# SCH_directMessage.net
KiCad netlist of a schematic drawn in EasyEDA
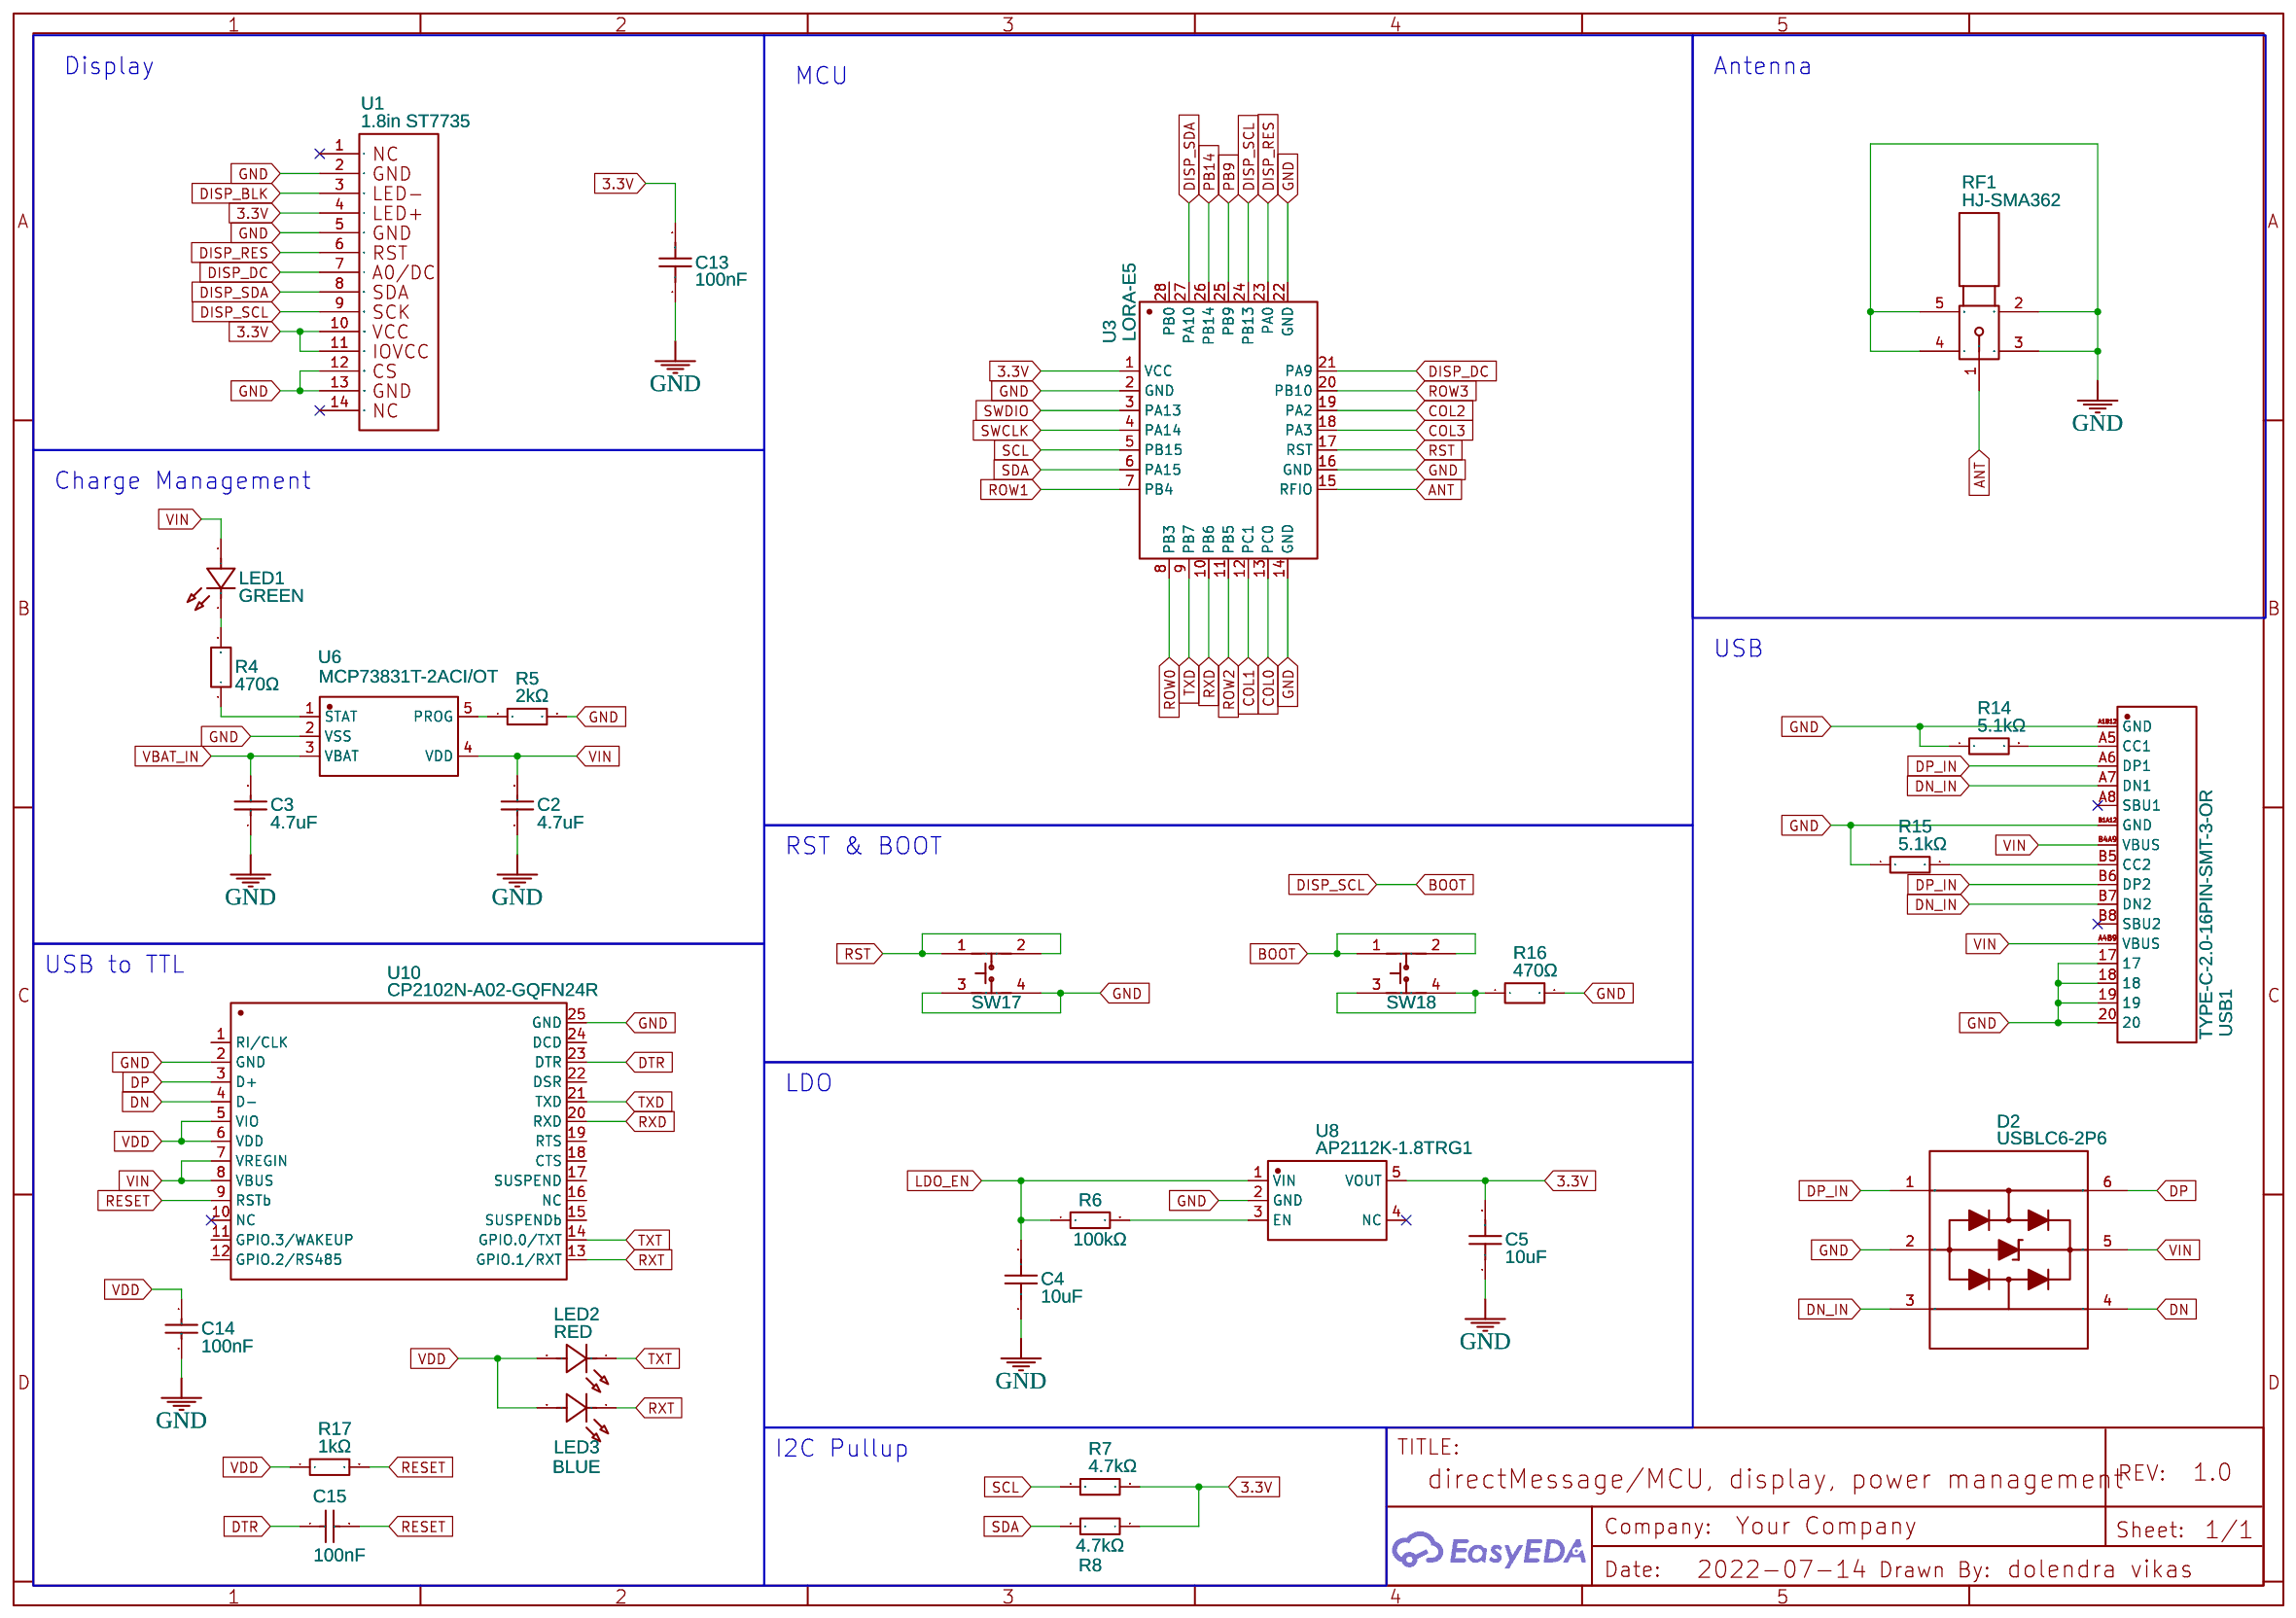
[diagram p0: Sheet_1]
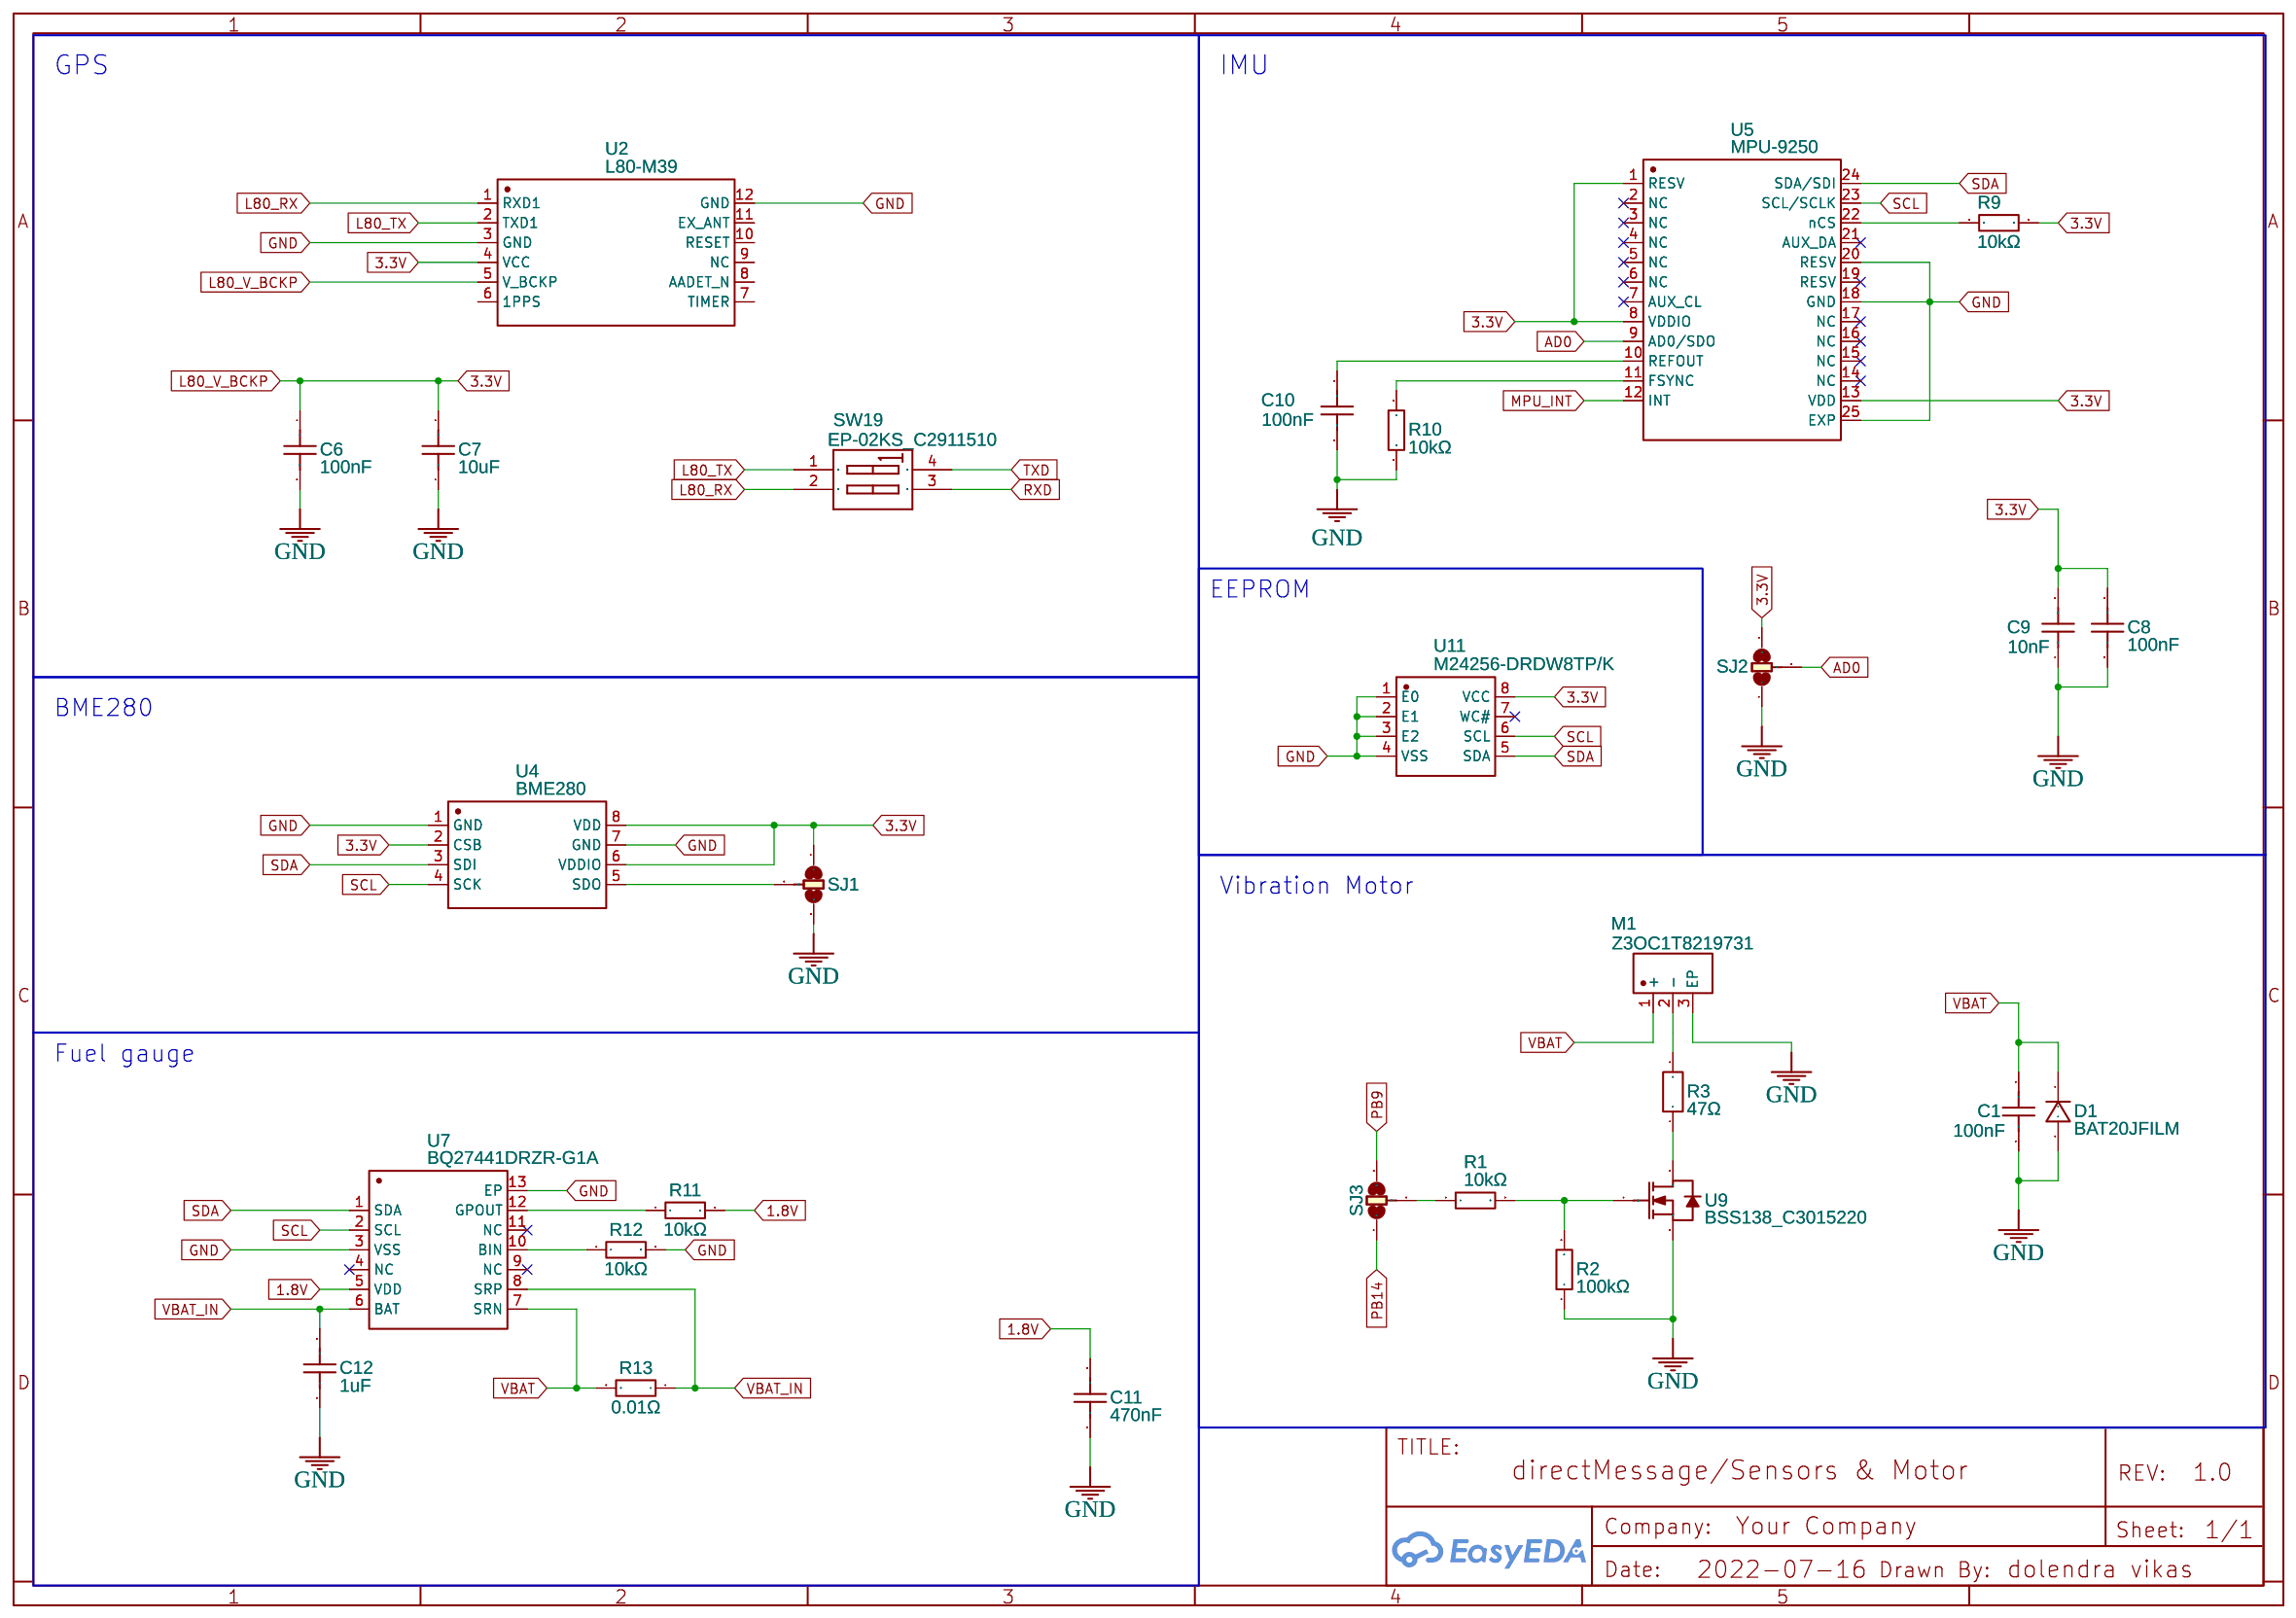
[diagram p1: Sheet_2]
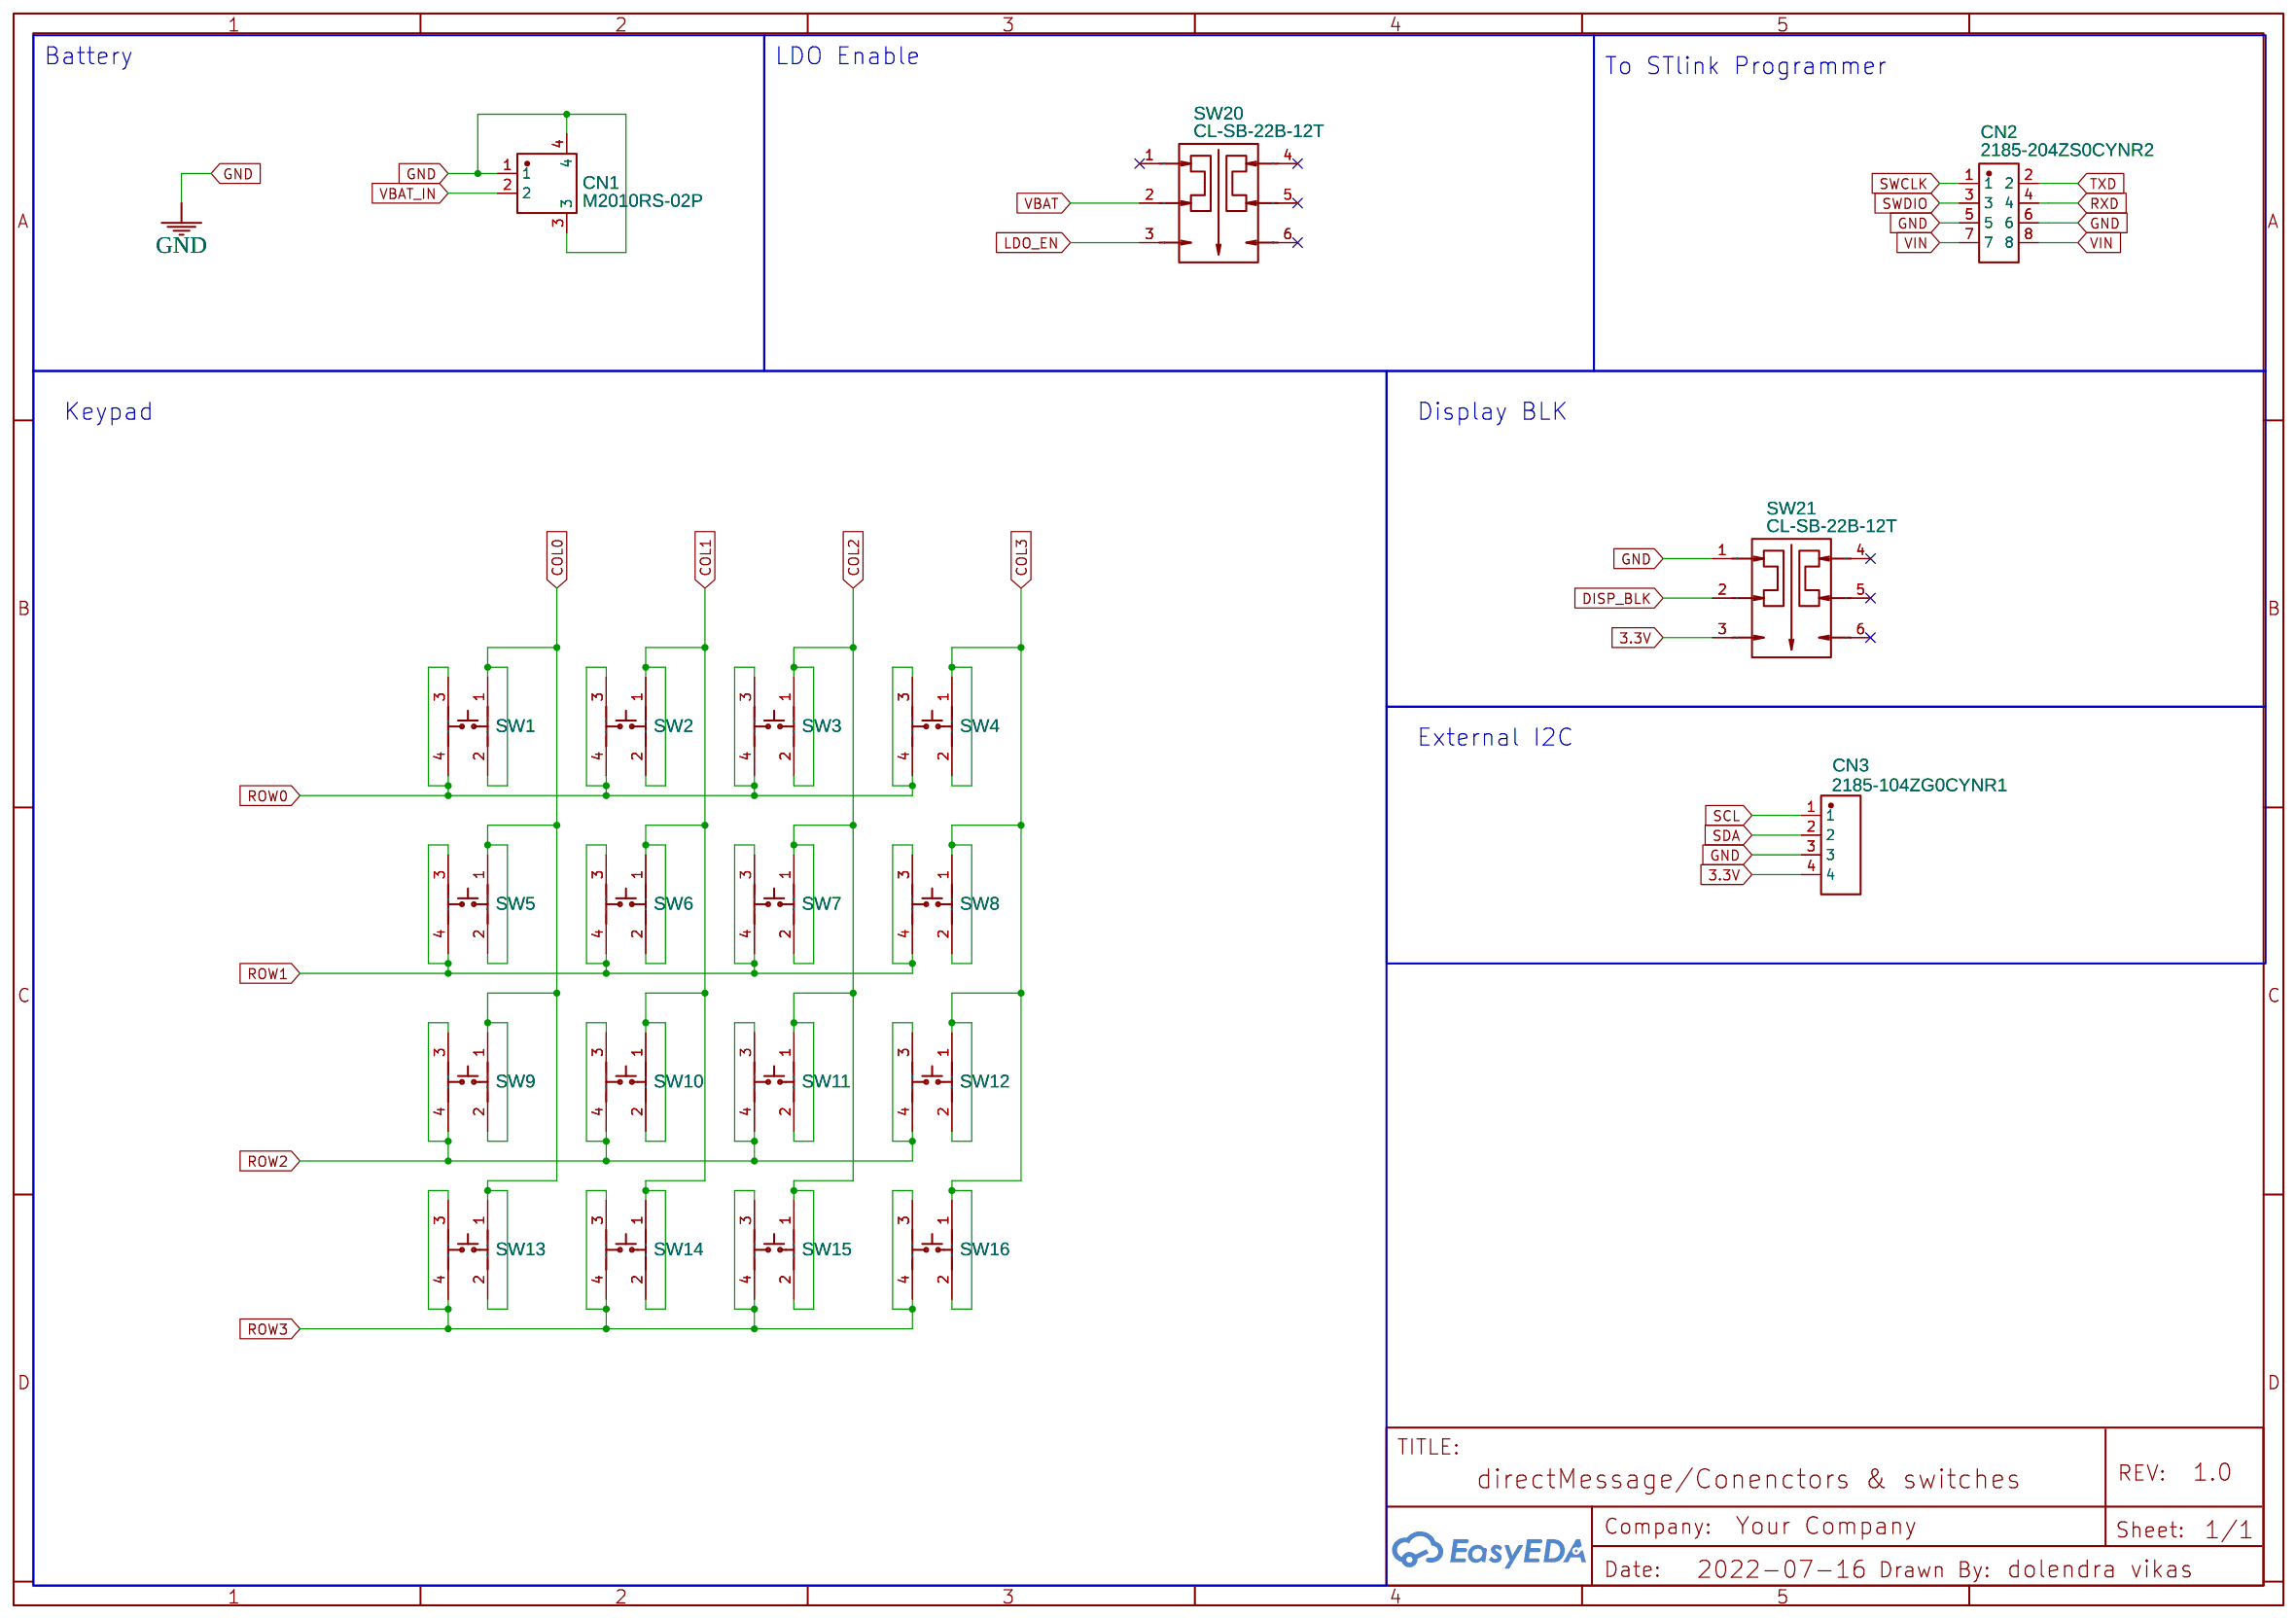
[diagram p2: Sheet_3]

(export (version "E")
  (design (tool "Eeschema 10.0.6"))
  (components
    (comp (ref "C2")
      (value "4.7uF")
      (fields
        (field (name "BOM_Manufacturer Part") "0603F475M100NT")
        (field (name "BOM_Supplier Part") "C108344")
      )
      (libsource (lib "") (part "0603 4.7UF CAPACITOR (SMD)"))
    )
    (comp (ref "C3")
      (value "4.7uF")
      (fields
        (field (name "BOM_Manufacturer Part") "0603F475M100NT")
        (field (name "BOM_Supplier Part") "C108344")
      )
      (libsource (lib "") (part "0603 4.7UF CAPACITOR (SMD)"))
    )
    (comp (ref "C4")
      (value "10uF")
      (fields
        (field (name "BOM_Manufacturer Part") "0603X106M6R3")
        (field (name "BOM_Supplier Part") "C123608")
      )
      (libsource (lib "") (part "0603X106M6R3"))
    )
    (comp (ref "C5")
      (value "10uF")
      (fields
        (field (name "BOM_Manufacturer Part") "0603X106M6R3")
        (field (name "BOM_Supplier Part") "C123608")
      )
      (libsource (lib "") (part "0603X106M6R3"))
    )
    (comp (ref "C13")
      (value "100nF")
      (fields
        (field (name "BOM_Manufacturer Part") "GCM188R71H104KA57D")
        (field (name "BOM_Supplier Part") "C85864")
      )
      (libsource (lib "") (part "GCM188R71H104KA57D"))
    )
    (comp (ref "C14")
      (value "100nF")
      (fields
        (field (name "BOM_Manufacturer Part") "FN18X104K500PBG")
        (field (name "BOM_Supplier Part") "C235731")
      )
      (libsource (lib "") (part "FN18X104K500PBG_1"))
    )
    (comp (ref "C15")
      (value "100nF")
      (fields
        (field (name "BOM_Manufacturer Part") "FN18X104K500PBG")
        (field (name "BOM_Supplier Part") "C235731")
      )
      (libsource (lib "") (part "FN18X104K500PBG"))
    )
    (comp (ref "D2")
      (value "USBLC6-2P6")
      (fields (field (name "BOM_Supplier Part") "C15999"))
      (libsource (lib "") (part "USBLC6-2P6"))
    )
    (comp (ref "LED1")
      (value "GREEN")
      (fields
        (field (name "BOM_Manufacturer Part") "XL-1608SYGC-06")
        (field (name "BOM_Supplier Part") "C965805")
      )
      (libsource (lib "") (part "XL-1608SYGC-06"))
    )
    (comp (ref "LED2")
      (value "RED")
      (fields
        (field (name "BOM_Manufacturer Part") "XL-1608SURC-06")
        (field (name "BOM_Supplier Part") "C965799")
      )
      (libsource (lib "") (part "XL-1608SURC-06"))
    )
    (comp (ref "LED3")
      (value "BLUE")
      (fields
        (field (name "BOM_Manufacturer Part") "XL-1608UBC-04")
        (field (name "BOM_Supplier Part") "C965807")
      )
      (libsource (lib "") (part "XL-1608UBC-04"))
    )
    (comp (ref "R4")
      (value "470Ω")
      (fields
        (field (name "BOM_Manufacturer Part") "ERJPA3J471V")
        (field (name "BOM_Supplier Part") "C441888")
      )
      (libsource (lib "") (part "ERJPA3J471V_1"))
    )
    (comp (ref "R5")
      (value "2kΩ")
      (fields
        (field (name "BOM_Manufacturer Part") "ERJ-3EKF2001V")
        (field (name "BOM_Supplier Part") "C192167")
      )
      (libsource (lib "") (part "ERJ-3EKF2001V"))
    )
    (comp (ref "R6")
      (value "100kΩ")
      (fields
        (field (name "BOM_Manufacturer Part") "ERJ3EKF1003V")
        (field (name "BOM_Supplier Part") "C189597")
      )
      (libsource (lib "") (part "ERJ3EKF1003V"))
    )
    (comp (ref "R7")
      (value "4.7kΩ")
      (fields
        (field (name "BOM_Manufacturer Part") "ERJ-3RBD4701V")
        (field (name "BOM_Supplier Part") "C191778")
      )
      (libsource (lib "") (part "ERJ-3RBD4701V_1"))
    )
    (comp (ref "R8")
      (value "4.7kΩ")
      (fields
        (field (name "BOM_Manufacturer Part") "ERJ-3RBD4701V")
        (field (name "BOM_Supplier Part") "C191778")
      )
      (libsource (lib "") (part "ERJ-3RBD4701V"))
    )
    (comp (ref "R14")
      (value "5.1kΩ")
      (fields
        (field (name "BOM_Manufacturer Part") "ERJ-3RBD5101V")
        (field (name "BOM_Supplier Part") "C191782")
      )
      (libsource (lib "") (part "ERJ-3RBD5101V"))
    )
    (comp (ref "R15")
      (value "5.1kΩ")
      (fields
        (field (name "BOM_Manufacturer Part") "ERJ-3RBD5101V")
        (field (name "BOM_Supplier Part") "C191782")
      )
      (libsource (lib "") (part "ERJ-3RBD5101V"))
    )
    (comp (ref "R16")
      (value "470Ω")
      (fields
        (field (name "BOM_Manufacturer Part") "ERJPA3J471V")
        (field (name "BOM_Supplier Part") "C441888")
      )
      (libsource (lib "") (part "ERJPA3J471V"))
    )
    (comp (ref "R17")
      (value "1kΩ")
      (fields
        (field (name "BOM_Manufacturer Part") "ERJ-3EKF1001V")
        (field (name "BOM_Supplier Part") "C118155")
      )
      (libsource (lib "") (part "ERJ-3EKF1001V"))
    )
    (comp (ref "RF1")
      (value "HJ-SMA362")
      (fields (field (name "BOM_Supplier Part") "C2905338"))
      (libsource (lib "") (part "HJ-SMA362"))
    )
    (comp (ref "SW17")
      (value "SKRPABE010")
      (fields (field (name "BOM_Supplier Part") "C115360"))
      (libsource (lib "") (part "SKRPABE010"))
    )
    (comp (ref "SW18")
      (value "SKRPABE010")
      (fields (field (name "BOM_Supplier Part") "C115360"))
      (libsource (lib "") (part "SKRPABE010"))
    )
    (comp (ref "U1") (value "1.8in ST7735") (libsource (lib "") (part "1.8in ST7735")))
    (comp (ref "U3")
      (value "LORA-E5")
      (fields
        (field (name "BOM_Manufacturer Part") "LoRa-E5")
        (field (name "BOM_Supplier Part") "C9900002286")
      )
      (libsource (lib "") (part "LORA-E5"))
    )
    (comp (ref "U6")
      (value "MCP73831T-2ACI/OT")
      (fields (field (name "BOM_Supplier Part") "C424093"))
      (libsource (lib "") (part "MCP73831T-2ACI/OT"))
    )
    (comp (ref "U8")
      (value "AP2112K-1.8TRG1")
      (fields (field (name "BOM_Supplier Part") "C176944"))
      (libsource (lib "") (part "AP2112K-1.8TRG1"))
    )
    (comp (ref "U10")
      (value "CP2102N-A02-GQFN24R")
      (fields (field (name "BOM_Supplier Part") "C969151"))
      (libsource (lib "") (part "CP2102N-A02-GQFN24R"))
    )
    (comp (ref "USB1")
      (value "TYPE-C-2.0-16PIN-SMT-3-OR")
      (fields (field (name "BOM_Supplier Part") "C2987387"))
      (libsource (lib "") (part "TYPE-C-2.0-16PIN-SMT-3-OR"))
    )
    (comp (ref "C1")
      (value "100nF")
      (fields
        (field (name "BOM_Manufacturer Part") "C0603C104J5RAC")
        (field (name "BOM_Supplier Part") "C490602")
      )
      (libsource (lib "") (part "C0603C104J5RAC"))
    )
    (comp (ref "C6")
      (value "100nF")
      (fields
        (field (name "BOM_Manufacturer Part") "C0603C104J5RAC")
        (field (name "BOM_Supplier Part") "C490602")
      )
      (libsource (lib "") (part "C0603C104J5RAC"))
    )
    (comp (ref "C7")
      (value "10uF")
      (fields
        (field (name "BOM_Manufacturer Part") "0603X106M6R3")
        (field (name "BOM_Supplier Part") "C123608")
      )
      (libsource (lib "") (part "0603X106M6R3"))
    )
    (comp (ref "C8")
      (value "100nF")
      (fields
        (field (name "BOM_Manufacturer Part") "C0603C104J5RAC")
        (field (name "BOM_Supplier Part") "C490602")
      )
      (libsource (lib "") (part "C0603C104J5RAC"))
    )
    (comp (ref "C9")
      (value "10nF")
      (fields
        (field (name "BOM_Manufacturer Part") "C0603C103J3GAC7867")
        (field (name "BOM_Supplier Part") "C140951")
      )
      (libsource (lib "") (part "C0603C103J3GAC7867"))
    )
    (comp (ref "C10")
      (value "100nF")
      (fields
        (field (name "BOM_Manufacturer Part") "C0603C104J5RAC")
        (field (name "BOM_Supplier Part") "C490602")
      )
      (libsource (lib "") (part "C0603C104J5RAC"))
    )
    (comp (ref "C11")
      (value "470nF")
      (fields
        (field (name "BOM_Manufacturer Part") "GCM188R71E474KA64D")
        (field (name "BOM_Supplier Part") "C161219")
      )
      (libsource (lib "") (part "GCM188R71E474KA64D"))
    )
    (comp (ref "C12")
      (value "1uF")
      (fields
        (field (name "BOM_Manufacturer Part") "GRM188R61E105KA12D")
        (field (name "BOM_Supplier Part") "C77046")
      )
      (libsource (lib "") (part "GRM188R61E105KA12D"))
    )
    (comp (ref "D1")
      (value "BAT20JFILM")
      (fields (field (name "BOM_Supplier Part") "C155590"))
      (libsource (lib "") (part "BAT20JFILM"))
    )
    (comp (ref "M1")
      (value "Z3OC1T8219731")
      (fields (field (name "BOM_Supplier Part") "C2894731"))
      (libsource (lib "") (part "Z3OC1T8219731"))
    )
    (comp (ref "R1")
      (value "10kΩ")
      (fields
        (field (name "BOM_Manufacturer Part") "ERJ3GEYJ103V")
        (field (name "BOM_Supplier Part") "C169849")
      )
      (libsource (lib "") (part "ERJ3GEYJ103V_1"))
    )
    (comp (ref "R2")
      (value "100kΩ")
      (fields
        (field (name "BOM_Manufacturer Part") "ERJ3EKF1003V")
        (field (name "BOM_Supplier Part") "C189597")
      )
      (libsource (lib "") (part "ERJ3EKF1003V"))
    )
    (comp (ref "R3")
      (value "47Ω")
      (fields
        (field (name "BOM_Manufacturer Part") "ERJUP3D47R0V")
        (field (name "BOM_Supplier Part") "C491217")
      )
      (libsource (lib "") (part "ERJUP3D47R0V"))
    )
    (comp (ref "R9")
      (value "10kΩ")
      (fields
        (field (name "BOM_Manufacturer Part") "ERJ3GEYJ103V")
        (field (name "BOM_Supplier Part") "C169849")
      )
      (libsource (lib "") (part "ERJ3GEYJ103V_1"))
    )
    (comp (ref "R10")
      (value "10kΩ")
      (fields
        (field (name "BOM_Manufacturer Part") "ERJ3GEYJ103V")
        (field (name "BOM_Supplier Part") "C169849")
      )
      (libsource (lib "") (part "ERJ3GEYJ103V"))
    )
    (comp (ref "R11")
      (value "10kΩ")
      (fields
        (field (name "BOM_Manufacturer Part") "ERJ3GEYJ103V")
        (field (name "BOM_Supplier Part") "C169849")
      )
      (libsource (lib "") (part "ERJ3GEYJ103V_1"))
    )
    (comp (ref "R12")
      (value "10kΩ")
      (fields
        (field (name "BOM_Manufacturer Part") "ERJ3GEYJ103V")
        (field (name "BOM_Supplier Part") "C169849")
      )
      (libsource (lib "") (part "ERJ3GEYJ103V_1"))
    )
    (comp (ref "R13")
      (value "0.01Ω")
      (fields
        (field (name "BOM_Manufacturer Part") "RTT03R010FTP")
        (field (name "BOM_Supplier Part") "C158899")
      )
      (libsource (lib "") (part "RTT03R010FTP"))
    )
    (comp (ref "SJ1") (value "SOLDERJUMPER_2WAY-OLDS") (libsource (lib "") (part "SOLDERJUMPER_2WAY-OLDS_1")))
    (comp (ref "SJ2") (value "SOLDERJUMPER_2WAY-OLDS") (libsource (lib "") (part "SOLDERJUMPER_2WAY-OLDS")))
    (comp (ref "SJ3") (value "SOLDERJUMPER_2WAY-OLDS") (libsource (lib "") (part "SOLDERJUMPER_2WAY-OLDS")))
    (comp (ref "SW19")
      (value "EP-02KS_C2911510")
      (fields (field (name "BOM_Manufacturer Part") "EP-02KS") (field (name "BOM_Supplier Part") "C2911510"))
      (libsource (lib "") (part "EP-02KS_C2911510"))
    )
    (comp (ref "U2")
      (value "L80-M39")
      (fields (field (name "BOM_Supplier Part") "C133488"))
      (libsource (lib "") (part "L80-M39"))
    )
    (comp (ref "U4")
      (value "BME280")
      (fields (field (name "BOM_Supplier Part") "C92489"))
      (libsource (lib "") (part "BME280"))
    )
    (comp (ref "U5")
      (value "MPU-9250")
      (fields (field (name "BOM_Supplier Part") "C71459"))
      (libsource (lib "") (part "MPU-9250"))
    )
    (comp (ref "U7")
      (value "BQ27441DRZR-G1A")
      (fields (field (name "BOM_Supplier Part") "C473397"))
      (libsource (lib "") (part "BQ27441DRZR-G1A"))
    )
    (comp (ref "U9")
      (value "BSS138_C3015220")
      (fields (field (name "BOM_Manufacturer Part") "BSS138") (field (name "BOM_Supplier Part") "C3015220"))
      (libsource (lib "") (part "BSS138_C3015220"))
    )
    (comp (ref "U11")
      (value "M24256-DRDW8TP/K")
      (fields (field (name "BOM_Supplier Part") "C2061704"))
      (libsource (lib "") (part "M24256-DRDW8TP/K"))
    )
    (comp (ref "CN1")
      (value "M2010RS-02P")
      (fields (field (name "BOM_Supplier Part") "C520130"))
      (libsource (lib "") (part "M2010RS-02P"))
    )
    (comp (ref "CN2")
      (value "2185-204ZS0CYNR2")
      (fields (field (name "BOM_Supplier Part") "C721893"))
      (libsource (lib "") (part "2185-204ZS0CYNR2"))
    )
    (comp (ref "CN3")
      (value "2185-104ZG0CYNR1")
      (fields (field (name "BOM_Supplier Part") "C721891"))
      (libsource (lib "") (part "2185-104ZG0CYNR1"))
    )
    (comp (ref "SW1")
      (value "SKRPABE010")
      (fields (field (name "BOM_Supplier Part") "C115360"))
      (libsource (lib "") (part "SKRPABE010"))
    )
    (comp (ref "SW2")
      (value "SKRPABE010")
      (fields (field (name "BOM_Supplier Part") "C115360"))
      (libsource (lib "") (part "SKRPABE010"))
    )
    (comp (ref "SW3")
      (value "SKRPABE010")
      (fields (field (name "BOM_Supplier Part") "C115360"))
      (libsource (lib "") (part "SKRPABE010"))
    )
    (comp (ref "SW4")
      (value "SKRPABE010")
      (fields (field (name "BOM_Supplier Part") "C115360"))
      (libsource (lib "") (part "SKRPABE010"))
    )
    (comp (ref "SW5")
      (value "SKRPABE010")
      (fields (field (name "BOM_Supplier Part") "C115360"))
      (libsource (lib "") (part "SKRPABE010"))
    )
    (comp (ref "SW6")
      (value "SKRPABE010")
      (fields (field (name "BOM_Supplier Part") "C115360"))
      (libsource (lib "") (part "SKRPABE010"))
    )
    (comp (ref "SW7")
      (value "SKRPABE010")
      (fields (field (name "BOM_Supplier Part") "C115360"))
      (libsource (lib "") (part "SKRPABE010"))
    )
    (comp (ref "SW8")
      (value "SKRPABE010")
      (fields (field (name "BOM_Supplier Part") "C115360"))
      (libsource (lib "") (part "SKRPABE010"))
    )
    (comp (ref "SW9")
      (value "SKRPABE010")
      (fields (field (name "BOM_Supplier Part") "C115360"))
      (libsource (lib "") (part "SKRPABE010"))
    )
    (comp (ref "SW10")
      (value "SKRPABE010")
      (fields (field (name "BOM_Supplier Part") "C115360"))
      (libsource (lib "") (part "SKRPABE010"))
    )
    (comp (ref "SW11")
      (value "SKRPABE010")
      (fields (field (name "BOM_Supplier Part") "C115360"))
      (libsource (lib "") (part "SKRPABE010"))
    )
    (comp (ref "SW12")
      (value "SKRPABE010")
      (fields (field (name "BOM_Supplier Part") "C115360"))
      (libsource (lib "") (part "SKRPABE010"))
    )
    (comp (ref "SW13")
      (value "SKRPABE010")
      (fields (field (name "BOM_Supplier Part") "C115360"))
      (libsource (lib "") (part "SKRPABE010"))
    )
    (comp (ref "SW14")
      (value "SKRPABE010")
      (fields (field (name "BOM_Supplier Part") "C115360"))
      (libsource (lib "") (part "SKRPABE010"))
    )
    (comp (ref "SW15")
      (value "SKRPABE010")
      (fields (field (name "BOM_Supplier Part") "C115360"))
      (libsource (lib "") (part "SKRPABE010"))
    )
    (comp (ref "SW16")
      (value "SKRPABE010")
      (fields (field (name "BOM_Supplier Part") "C115360"))
      (libsource (lib "") (part "SKRPABE010"))
    )
    (comp (ref "SW20")
      (value "CL-SB-22B-12T")
      (fields (field (name "BOM_Supplier Part") "C2921665"))
      (libsource (lib "") (part "CL-SB-22B-12T"))
    )
    (comp (ref "SW21")
      (value "CL-SB-22B-12T")
      (fields (field (name "BOM_Supplier Part") "C2921665"))
      (libsource (lib "") (part "CL-SB-22B-12T"))
    )
  )
  (nets
    (net (code "1") (name "1.8V") (class "Default")
      (node (ref "C11") (pin "2") (pinfunction "2_2") (pintype "unspecified"))
      (node (ref "R11") (pin "2") (pinfunction "2_2") (pintype "unspecified"))
      (node (ref "U7") (pin "5") (pinfunction "VDD_5") (pintype "unspecified"))
    )
    (net (code "2") (name "3.3V") (class "Default")
      (node (ref "C13") (pin "2") (pinfunction "2_2") (pintype "unspecified"))
      (node (ref "C5") (pin "2") (pinfunction "2_2") (pintype "unspecified"))
      (node (ref "C6") (pin "1") (pinfunction "1_1") (pintype "unspecified"))
      (node (ref "C7") (pin "2") (pinfunction "2_2") (pintype "unspecified"))
      (node (ref "C8") (pin "1") (pinfunction "1_1") (pintype "unspecified"))
      (node (ref "C9") (pin "2") (pinfunction "2_2") (pintype "unspecified"))
      (node (ref "CN3") (pin "4") (pinfunction "4_4") (pintype "unspecified"))
      (node (ref "R7") (pin "2") (pinfunction "2_2") (pintype "unspecified"))
      (node (ref "R8") (pin "1") (pinfunction "1_1") (pintype "unspecified"))
      (node (ref "R9") (pin "2") (pinfunction "2_2") (pintype "unspecified"))
      (node (ref "SJ1") (pin "1") (pinfunction "1_1") (pintype "unspecified"))
      (node (ref "SJ2") (pin "3") (pinfunction "3_3") (pintype "unspecified"))
      (node (ref "SW21") (pin "3") (pinfunction "3_3") (pintype "unspecified"))
      (node (ref "U1") (pin "10") (pinfunction "10_10") (pintype "unspecified"))
      (node (ref "U1") (pin "11") (pinfunction "11_11") (pintype "unspecified"))
      (node (ref "U1") (pin "4") (pinfunction "4_4") (pintype "unspecified"))
      (node (ref "U11") (pin "8") (pinfunction "VCC_8") (pintype "unspecified"))
      (node (ref "U2") (pin "4") (pinfunction "VCC_4") (pintype "unspecified"))
      (node (ref "U2") (pin "5") (pinfunction "V_BCKP_5") (pintype "unspecified"))
      (node (ref "U3") (pin "1") (pinfunction "VCC_1") (pintype "unspecified"))
      (node (ref "U4") (pin "2") (pinfunction "CSB_2") (pintype "unspecified"))
      (node (ref "U4") (pin "6") (pinfunction "VDDIO_6") (pintype "unspecified"))
      (node (ref "U4") (pin "8") (pinfunction "VDD_8") (pintype "unspecified"))
      (node (ref "U5") (pin "1") (pinfunction "RESV_1") (pintype "unspecified"))
      (node (ref "U5") (pin "13") (pinfunction "VDD_13") (pintype "unspecified"))
      (node (ref "U5") (pin "8") (pinfunction "VDDIO_8") (pintype "unspecified"))
      (node (ref "U8") (pin "5") (pinfunction "VOUT_5") (pintype "unspecified"))
    )
    (net (code "3") (name "AD0") (class "Default")
      (node (ref "SJ2") (pin "2") (pinfunction "2_2") (pintype "unspecified"))
      (node (ref "U5") (pin "9") (pinfunction "AD0/SDO_9") (pintype "unspecified"))
    )
    (net (code "4") (name "ANT") (class "Default")
      (node (ref "RF1") (pin "1") (pinfunction "1_1") (pintype "unspecified"))
      (node (ref "U3") (pin "15") (pinfunction "RFIO_15") (pintype "unspecified"))
    )
    (net (code "5") (name "BOOT") (class "Default")
      (node (ref "SW18") (pin "1") (pinfunction "1_1") (pintype "unspecified"))
      (node (ref "SW18") (pin "2") (pinfunction "2_2") (pintype "unspecified"))
      (node (ref "U1") (pin "9") (pinfunction "9_9") (pintype "unspecified"))
      (node (ref "U3") (pin "24") (pinfunction "PB13_24") (pintype "unspecified"))
    )
    (net (code "6") (name "COL0") (class "Default")
      (node (ref "SW1") (pin "1") (pinfunction "1_1") (pintype "unspecified"))
      (node (ref "SW1") (pin "2") (pinfunction "2_2") (pintype "unspecified"))
      (node (ref "SW13") (pin "1") (pinfunction "1_1") (pintype "unspecified"))
      (node (ref "SW13") (pin "2") (pinfunction "2_2") (pintype "unspecified"))
      (node (ref "SW5") (pin "1") (pinfunction "1_1") (pintype "unspecified"))
      (node (ref "SW5") (pin "2") (pinfunction "2_2") (pintype "unspecified"))
      (node (ref "SW9") (pin "1") (pinfunction "1_1") (pintype "unspecified"))
      (node (ref "SW9") (pin "2") (pinfunction "2_2") (pintype "unspecified"))
      (node (ref "U3") (pin "13") (pinfunction "PC0_13") (pintype "unspecified"))
    )
    (net (code "7") (name "COL1") (class "Default")
      (node (ref "SW10") (pin "1") (pinfunction "1_1") (pintype "unspecified"))
      (node (ref "SW10") (pin "2") (pinfunction "2_2") (pintype "unspecified"))
      (node (ref "SW14") (pin "1") (pinfunction "1_1") (pintype "unspecified"))
      (node (ref "SW14") (pin "2") (pinfunction "2_2") (pintype "unspecified"))
      (node (ref "SW2") (pin "1") (pinfunction "1_1") (pintype "unspecified"))
      (node (ref "SW2") (pin "2") (pinfunction "2_2") (pintype "unspecified"))
      (node (ref "SW6") (pin "1") (pinfunction "1_1") (pintype "unspecified"))
      (node (ref "SW6") (pin "2") (pinfunction "2_2") (pintype "unspecified"))
      (node (ref "U3") (pin "12") (pinfunction "PC1_12") (pintype "unspecified"))
    )
    (net (code "8") (name "COL2") (class "Default")
      (node (ref "SW11") (pin "1") (pinfunction "1_1") (pintype "unspecified"))
      (node (ref "SW11") (pin "2") (pinfunction "2_2") (pintype "unspecified"))
      (node (ref "SW15") (pin "1") (pinfunction "1_1") (pintype "unspecified"))
      (node (ref "SW15") (pin "2") (pinfunction "2_2") (pintype "unspecified"))
      (node (ref "SW3") (pin "1") (pinfunction "1_1") (pintype "unspecified"))
      (node (ref "SW3") (pin "2") (pinfunction "2_2") (pintype "unspecified"))
      (node (ref "SW7") (pin "1") (pinfunction "1_1") (pintype "unspecified"))
      (node (ref "SW7") (pin "2") (pinfunction "2_2") (pintype "unspecified"))
      (node (ref "U3") (pin "19") (pinfunction "PA2_19") (pintype "unspecified"))
    )
    (net (code "9") (name "COL3") (class "Default")
      (node (ref "SW12") (pin "1") (pinfunction "1_1") (pintype "unspecified"))
      (node (ref "SW12") (pin "2") (pinfunction "2_2") (pintype "unspecified"))
      (node (ref "SW16") (pin "1") (pinfunction "1_1") (pintype "unspecified"))
      (node (ref "SW16") (pin "2") (pinfunction "2_2") (pintype "unspecified"))
      (node (ref "SW4") (pin "1") (pinfunction "1_1") (pintype "unspecified"))
      (node (ref "SW4") (pin "2") (pinfunction "2_2") (pintype "unspecified"))
      (node (ref "SW8") (pin "1") (pinfunction "1_1") (pintype "unspecified"))
      (node (ref "SW8") (pin "2") (pinfunction "2_2") (pintype "unspecified"))
      (node (ref "U3") (pin "18") (pinfunction "PA3_18") (pintype "unspecified"))
    )
    (net (code "10") (name "DISP_BLK") (class "Default")
      (node (ref "SW21") (pin "2") (pinfunction "2_2") (pintype "unspecified"))
      (node (ref "U1") (pin "3") (pinfunction "3_3") (pintype "unspecified"))
    )
    (net (code "11") (name "DISP_DC") (class "Default")
      (node (ref "U1") (pin "7") (pinfunction "7_7") (pintype "unspecified"))
      (node (ref "U3") (pin "21") (pinfunction "PA9_21") (pintype "unspecified"))
    )
    (net (code "12") (name "DISP_RES") (class "Default")
      (node (ref "U1") (pin "6") (pinfunction "6_6") (pintype "unspecified"))
      (node (ref "U3") (pin "23") (pinfunction "PA0_23") (pintype "unspecified"))
    )
    (net (code "13") (name "DISP_SDA") (class "Default")
      (node (ref "U1") (pin "8") (pinfunction "8_8") (pintype "unspecified"))
      (node (ref "U3") (pin "27") (pinfunction "PA10_27") (pintype "unspecified"))
    )
    (net (code "14") (name "DN") (class "Default")
      (node (ref "D2") (pin "4") (pinfunction "I/O2_4") (pintype "input"))
      (node (ref "U10") (pin "4") (pinfunction "D-_4") (pintype "unspecified"))
    )
    (net (code "15") (name "DN_IN") (class "Default")
      (node (ref "D2") (pin "3") (pinfunction "I/O2_3") (pintype "input"))
      (node (ref "USB1") (pin "A7") (pinfunction "DN1_A7") (pintype "unspecified"))
      (node (ref "USB1") (pin "B7") (pinfunction "DN2_B7") (pintype "unspecified"))
    )
    (net (code "16") (name "DP") (class "Default")
      (node (ref "D2") (pin "6") (pinfunction "I/O1_6") (pintype "input"))
      (node (ref "U10") (pin "3") (pinfunction "D+_3") (pintype "unspecified"))
    )
    (net (code "17") (name "DP_IN") (class "Default")
      (node (ref "D2") (pin "1") (pinfunction "I/O1_1") (pintype "input"))
      (node (ref "USB1") (pin "A6") (pinfunction "DP1_A6") (pintype "unspecified"))
      (node (ref "USB1") (pin "B6") (pinfunction "DP2_B6") (pintype "unspecified"))
    )
    (net (code "18") (name "DTR") (class "Default")
      (node (ref "C15") (pin "1") (pinfunction "1_1") (pintype "input"))
      (node (ref "U10") (pin "23") (pinfunction "DTR_23") (pintype "unspecified"))
    )
    (net (code "19") (name "GND") (class "Default")
      (node (ref "C1") (pin "2") (pinfunction "2_2") (pintype "unspecified"))
      (node (ref "C10") (pin "2") (pinfunction "2_2") (pintype "unspecified"))
      (node (ref "C11") (pin "1") (pinfunction "1_1") (pintype "unspecified"))
      (node (ref "C12") (pin "1") (pinfunction "1_1") (pintype "unspecified"))
      (node (ref "C13") (pin "1") (pinfunction "1_1") (pintype "unspecified"))
      (node (ref "C14") (pin "2") (pinfunction "2_2") (pintype "input"))
      (node (ref "C2") (pin "1") (pinfunction "1_1") (pintype "input"))
      (node (ref "C3") (pin "1") (pinfunction "1_1") (pintype "input"))
      (node (ref "C4") (pin "1") (pinfunction "1_1") (pintype "unspecified"))
      (node (ref "C5") (pin "1") (pinfunction "1_1") (pintype "unspecified"))
      (node (ref "C6") (pin "2") (pinfunction "2_2") (pintype "unspecified"))
      (node (ref "C7") (pin "1") (pinfunction "1_1") (pintype "unspecified"))
      (node (ref "C8") (pin "2") (pinfunction "2_2") (pintype "unspecified"))
      (node (ref "C9") (pin "1") (pinfunction "1_1") (pintype "unspecified"))
      (node (ref "CN1") (pin "1") (pinfunction "1_1") (pintype "unspecified"))
      (node (ref "CN1") (pin "3") (pinfunction "3_3") (pintype "unspecified"))
      (node (ref "CN1") (pin "4") (pinfunction "4_4") (pintype "unspecified"))
      (node (ref "CN2") (pin "5") (pinfunction "5_5") (pintype "unspecified"))
      (node (ref "CN2") (pin "6") (pinfunction "6_6") (pintype "unspecified"))
      (node (ref "CN3") (pin "3") (pinfunction "3_3") (pintype "unspecified"))
      (node (ref "D1") (pin "2") (pinfunction "A_2") (pintype "unspecified"))
      (node (ref "D2") (pin "2") (pinfunction "GND_2") (pintype "input"))
      (node (ref "M1") (pin "3") (pinfunction "EP_3") (pintype "unspecified"))
      (node (ref "R10") (pin "2") (pinfunction "2_2") (pintype "unspecified"))
      (node (ref "R12") (pin "2") (pinfunction "2_2") (pintype "unspecified"))
      (node (ref "R14") (pin "1") (pinfunction "1_1") (pintype "unspecified"))
      (node (ref "R15") (pin "1") (pinfunction "1_1") (pintype "unspecified"))
      (node (ref "R16") (pin "2") (pinfunction "2_2") (pintype "unspecified"))
      (node (ref "R2") (pin "1") (pinfunction "1_1") (pintype "unspecified"))
      (node (ref "R5") (pin "2") (pinfunction "2_2") (pintype "unspecified"))
      (node (ref "RF1") (pin "2") (pinfunction "2_2") (pintype "unspecified"))
      (node (ref "RF1") (pin "3") (pinfunction "3_3") (pintype "unspecified"))
      (node (ref "RF1") (pin "4") (pinfunction "4_4") (pintype "unspecified"))
      (node (ref "RF1") (pin "5") (pinfunction "5_5") (pintype "unspecified"))
      (node (ref "SJ1") (pin "3") (pinfunction "3_3") (pintype "unspecified"))
      (node (ref "SJ2") (pin "1") (pinfunction "1_1") (pintype "unspecified"))
      (node (ref "SW17") (pin "3") (pinfunction "3_3") (pintype "unspecified"))
      (node (ref "SW17") (pin "4") (pinfunction "4_4") (pintype "unspecified"))
      (node (ref "SW21") (pin "1") (pinfunction "1_1") (pintype "unspecified"))
      (node (ref "U1") (pin "12") (pinfunction "12_12") (pintype "unspecified"))
      (node (ref "U1") (pin "13") (pinfunction "13_13") (pintype "unspecified"))
      (node (ref "U1") (pin "2") (pinfunction "2_2") (pintype "unspecified"))
      (node (ref "U1") (pin "5") (pinfunction "5_5") (pintype "unspecified"))
      (node (ref "U10") (pin "2") (pinfunction "GND_2") (pintype "unspecified"))
      (node (ref "U10") (pin "25") (pinfunction "GND_25") (pintype "unspecified"))
      (node (ref "U11") (pin "1") (pinfunction "E0_1") (pintype "unspecified"))
      (node (ref "U11") (pin "2") (pinfunction "E1_2") (pintype "unspecified"))
      (node (ref "U11") (pin "3") (pinfunction "E2_3") (pintype "unspecified"))
      (node (ref "U11") (pin "4") (pinfunction "VSS_4") (pintype "unspecified"))
      (node (ref "U2") (pin "12") (pinfunction "GND_12") (pintype "unspecified"))
      (node (ref "U2") (pin "3") (pinfunction "GND_3") (pintype "unspecified"))
      (node (ref "U3") (pin "14") (pinfunction "GND_14") (pintype "unspecified"))
      (node (ref "U3") (pin "16") (pinfunction "GND_16") (pintype "unspecified"))
      (node (ref "U3") (pin "2") (pinfunction "GND_2") (pintype "unspecified"))
      (node (ref "U3") (pin "22") (pinfunction "GND_22") (pintype "unspecified"))
      (node (ref "U4") (pin "1") (pinfunction "GND_1") (pintype "unspecified"))
      (node (ref "U4") (pin "7") (pinfunction "GND_7") (pintype "unspecified"))
      (node (ref "U5") (pin "18") (pinfunction "GND_18") (pintype "unspecified"))
      (node (ref "U5") (pin "20") (pinfunction "RESV_20") (pintype "unspecified"))
      (node (ref "U5") (pin "25") (pinfunction "EXP_25") (pintype "unspecified"))
      (node (ref "U6") (pin "2") (pinfunction "VSS_2") (pintype "unspecified"))
      (node (ref "U7") (pin "13") (pinfunction "EP_13") (pintype "unspecified"))
      (node (ref "U7") (pin "3") (pinfunction "VSS_3") (pintype "unspecified"))
      (node (ref "U8") (pin "2") (pinfunction "GND_2") (pintype "unspecified"))
      (node (ref "U9") (pin "2") (pinfunction "S_2") (pintype "unspecified"))
      (node (ref "USB1") (pin "17") (pinfunction "17_17") (pintype "unspecified"))
      (node (ref "USB1") (pin "18") (pinfunction "18_18") (pintype "unspecified"))
      (node (ref "USB1") (pin "19") (pinfunction "19_19") (pintype "unspecified"))
      (node (ref "USB1") (pin "20") (pinfunction "20_20") (pintype "unspecified"))
      (node (ref "USB1") (pin "A1B12") (pinfunction "GND_A1B12") (pintype "unspecified"))
      (node (ref "USB1") (pin "B1A12") (pinfunction "GND_B1A12") (pintype "unspecified"))
    )
    (net (code "20") (name "L80_RX") (class "Default")
      (node (ref "SW19") (pin "2") (pinfunction "A2_2") (pintype "input"))
      (node (ref "U2") (pin "1") (pinfunction "RXD1_1") (pintype "unspecified"))
    )
    (net (code "21") (name "L80_TX") (class "Default")
      (node (ref "SW19") (pin "1") (pinfunction "A1_1") (pintype "input"))
      (node (ref "U2") (pin "2") (pinfunction "TXD1_2") (pintype "unspecified"))
    )
    (net (code "22") (name "LDO_EN") (class "Default")
      (node (ref "C4") (pin "2") (pinfunction "2_2") (pintype "unspecified"))
      (node (ref "R6") (pin "1") (pinfunction "1_1") (pintype "unspecified"))
      (node (ref "SW20") (pin "3") (pinfunction "3_3") (pintype "unspecified"))
      (node (ref "U8") (pin "1") (pinfunction "VIN_1") (pintype "unspecified"))
    )
    (net (code "23") (name "MPU_INT") (class "Default")
      (node (ref "U5") (pin "12") (pinfunction "INT_12") (pintype "unspecified"))
    )
    (net (code "24") (name "Net-(LED1-K)") (class "Default")
      (node (ref "LED1") (pin "1") (pinfunction "K_1") (pintype "unspecified"))
      (node (ref "R4") (pin "2") (pinfunction "2_2") (pintype "unspecified"))
    )
    (net (code "25") (name "Net-(M1--)") (class "Default")
      (node (ref "M1") (pin "2") (pinfunction "-_2") (pintype "unspecified"))
      (node (ref "R3") (pin "2") (pinfunction "2_2") (pintype "unspecified"))
    )
    (net (code "26") (name "Net-(R1-Pad1)") (class "Default")
      (node (ref "R1") (pin "1") (pinfunction "1_1") (pintype "unspecified"))
      (node (ref "SJ3") (pin "2") (pinfunction "2_2") (pintype "unspecified"))
    )
    (net (code "27") (name "Net-(R16-Pad1)") (class "Default")
      (node (ref "R16") (pin "1") (pinfunction "1_1") (pintype "unspecified"))
      (node (ref "SW18") (pin "3") (pinfunction "3_3") (pintype "unspecified"))
      (node (ref "SW18") (pin "4") (pinfunction "4_4") (pintype "unspecified"))
    )
    (net (code "28") (name "Net-(U4-SDO)") (class "Default")
      (node (ref "SJ1") (pin "2") (pinfunction "2_2") (pintype "unspecified"))
      (node (ref "U4") (pin "5") (pinfunction "SDO_5") (pintype "unspecified"))
    )
    (net (code "29") (name "Net-(U5-FSYNC)") (class "Default")
      (node (ref "R10") (pin "1") (pinfunction "1_1") (pintype "unspecified"))
      (node (ref "U5") (pin "11") (pinfunction "FSYNC_11") (pintype "unspecified"))
    )
    (net (code "30") (name "Net-(U5-REFOUT)") (class "Default")
      (node (ref "C10") (pin "1") (pinfunction "1_1") (pintype "unspecified"))
      (node (ref "U5") (pin "10") (pinfunction "REFOUT_10") (pintype "unspecified"))
    )
    (net (code "31") (name "Net-(U5-nCS)") (class "Default")
      (node (ref "R9") (pin "1") (pinfunction "1_1") (pintype "unspecified"))
      (node (ref "U5") (pin "22") (pinfunction "nCS_22") (pintype "unspecified"))
    )
    (net (code "32") (name "Net-(U6-PROG)") (class "Default")
      (node (ref "R5") (pin "1") (pinfunction "1_1") (pintype "unspecified"))
      (node (ref "U6") (pin "5") (pinfunction "PROG_5") (pintype "unspecified"))
    )
    (net (code "33") (name "Net-(U6-STAT)") (class "Default")
      (node (ref "R4") (pin "1") (pinfunction "1_1") (pintype "unspecified"))
      (node (ref "U6") (pin "1") (pinfunction "STAT_1") (pintype "unspecified"))
    )
    (net (code "34") (name "Net-(U7-BIN)") (class "Default")
      (node (ref "R12") (pin "1") (pinfunction "1_1") (pintype "unspecified"))
      (node (ref "U7") (pin "10") (pinfunction "BIN_10") (pintype "unspecified"))
    )
    (net (code "35") (name "Net-(U7-GPOUT)") (class "Default")
      (node (ref "R11") (pin "1") (pinfunction "1_1") (pintype "unspecified"))
      (node (ref "U7") (pin "12") (pinfunction "GPOUT_12") (pintype "unspecified"))
    )
    (net (code "36") (name "Net-(U8-EN)") (class "Default")
      (node (ref "R6") (pin "2") (pinfunction "2_2") (pintype "unspecified"))
      (node (ref "U8") (pin "3") (pinfunction "EN_3") (pintype "unspecified"))
    )
    (net (code "37") (name "Net-(U9-D)") (class "Default")
      (node (ref "R3") (pin "1") (pinfunction "1_1") (pintype "unspecified"))
      (node (ref "U9") (pin "3") (pinfunction "D_3") (pintype "unspecified"))
    )
    (net (code "38") (name "Net-(U9-G)") (class "Default")
      (node (ref "R1") (pin "2") (pinfunction "2_2") (pintype "unspecified"))
      (node (ref "R2") (pin "2") (pinfunction "2_2") (pintype "unspecified"))
      (node (ref "U9") (pin "1") (pinfunction "G_1") (pintype "unspecified"))
    )
    (net (code "39") (name "Net-(USB1-CC1)") (class "Default")
      (node (ref "R14") (pin "2") (pinfunction "2_2") (pintype "unspecified"))
      (node (ref "USB1") (pin "A5") (pinfunction "CC1_A5") (pintype "unspecified"))
    )
    (net (code "40") (name "Net-(USB1-CC2)") (class "Default")
      (node (ref "R15") (pin "2") (pinfunction "2_2") (pintype "unspecified"))
      (node (ref "USB1") (pin "B5") (pinfunction "CC2_B5") (pintype "unspecified"))
    )
    (net (code "41") (name "PB9") (class "Default")
      (node (ref "SJ3") (pin "3") (pinfunction "3_3") (pintype "unspecified"))
      (node (ref "U3") (pin "25") (pinfunction "PB9_25") (pintype "unspecified"))
    )
    (net (code "42") (name "PB14") (class "Default")
      (node (ref "SJ3") (pin "1") (pinfunction "1_1") (pintype "unspecified"))
      (node (ref "U3") (pin "26") (pinfunction "PB14_26") (pintype "unspecified"))
    )
    (net (code "43") (name "RESET") (class "Default")
      (node (ref "C15") (pin "2") (pinfunction "2_2") (pintype "input"))
      (node (ref "R17") (pin "2") (pinfunction "2_2") (pintype "unspecified"))
      (node (ref "U10") (pin "9") (pinfunction "RSTb_9") (pintype "unspecified"))
    )
    (net (code "44") (name "ROW0") (class "Default")
      (node (ref "SW1") (pin "3") (pinfunction "3_3") (pintype "unspecified"))
      (node (ref "SW1") (pin "4") (pinfunction "4_4") (pintype "unspecified"))
      (node (ref "SW2") (pin "3") (pinfunction "3_3") (pintype "unspecified"))
      (node (ref "SW2") (pin "4") (pinfunction "4_4") (pintype "unspecified"))
      (node (ref "SW3") (pin "3") (pinfunction "3_3") (pintype "unspecified"))
      (node (ref "SW3") (pin "4") (pinfunction "4_4") (pintype "unspecified"))
      (node (ref "SW4") (pin "3") (pinfunction "3_3") (pintype "unspecified"))
      (node (ref "SW4") (pin "4") (pinfunction "4_4") (pintype "unspecified"))
      (node (ref "U3") (pin "8") (pinfunction "PB3_8") (pintype "unspecified"))
    )
    (net (code "45") (name "ROW1") (class "Default")
      (node (ref "SW5") (pin "3") (pinfunction "3_3") (pintype "unspecified"))
      (node (ref "SW5") (pin "4") (pinfunction "4_4") (pintype "unspecified"))
      (node (ref "SW6") (pin "3") (pinfunction "3_3") (pintype "unspecified"))
      (node (ref "SW6") (pin "4") (pinfunction "4_4") (pintype "unspecified"))
      (node (ref "SW7") (pin "3") (pinfunction "3_3") (pintype "unspecified"))
      (node (ref "SW7") (pin "4") (pinfunction "4_4") (pintype "unspecified"))
      (node (ref "SW8") (pin "3") (pinfunction "3_3") (pintype "unspecified"))
      (node (ref "SW8") (pin "4") (pinfunction "4_4") (pintype "unspecified"))
      (node (ref "U3") (pin "7") (pinfunction "PB4_7") (pintype "unspecified"))
    )
    (net (code "46") (name "ROW2") (class "Default")
      (node (ref "SW10") (pin "3") (pinfunction "3_3") (pintype "unspecified"))
      (node (ref "SW10") (pin "4") (pinfunction "4_4") (pintype "unspecified"))
      (node (ref "SW11") (pin "3") (pinfunction "3_3") (pintype "unspecified"))
      (node (ref "SW11") (pin "4") (pinfunction "4_4") (pintype "unspecified"))
      (node (ref "SW12") (pin "3") (pinfunction "3_3") (pintype "unspecified"))
      (node (ref "SW12") (pin "4") (pinfunction "4_4") (pintype "unspecified"))
      (node (ref "SW9") (pin "3") (pinfunction "3_3") (pintype "unspecified"))
      (node (ref "SW9") (pin "4") (pinfunction "4_4") (pintype "unspecified"))
      (node (ref "U3") (pin "11") (pinfunction "PB5_11") (pintype "unspecified"))
    )
    (net (code "47") (name "ROW3") (class "Default")
      (node (ref "SW13") (pin "3") (pinfunction "3_3") (pintype "unspecified"))
      (node (ref "SW13") (pin "4") (pinfunction "4_4") (pintype "unspecified"))
      (node (ref "SW14") (pin "3") (pinfunction "3_3") (pintype "unspecified"))
      (node (ref "SW14") (pin "4") (pinfunction "4_4") (pintype "unspecified"))
      (node (ref "SW15") (pin "3") (pinfunction "3_3") (pintype "unspecified"))
      (node (ref "SW15") (pin "4") (pinfunction "4_4") (pintype "unspecified"))
      (node (ref "SW16") (pin "3") (pinfunction "3_3") (pintype "unspecified"))
      (node (ref "SW16") (pin "4") (pinfunction "4_4") (pintype "unspecified"))
      (node (ref "U3") (pin "20") (pinfunction "PB10_20") (pintype "unspecified"))
    )
    (net (code "48") (name "RST") (class "Default")
      (node (ref "SW17") (pin "1") (pinfunction "1_1") (pintype "unspecified"))
      (node (ref "SW17") (pin "2") (pinfunction "2_2") (pintype "unspecified"))
      (node (ref "U3") (pin "17") (pinfunction "RST_17") (pintype "unspecified"))
    )
    (net (code "49") (name "RXD") (class "Default")
      (node (ref "CN2") (pin "4") (pinfunction "4_4") (pintype "unspecified"))
      (node (ref "SW19") (pin "3") (pinfunction "B2_3") (pintype "input"))
      (node (ref "U10") (pin "20") (pinfunction "RXD_20") (pintype "unspecified"))
      (node (ref "U3") (pin "10") (pinfunction "PB6_10") (pintype "unspecified"))
    )
    (net (code "50") (name "RXT") (class "Default")
      (node (ref "LED3") (pin "1") (pinfunction "K_1") (pintype "unspecified"))
      (node (ref "U10") (pin "13") (pinfunction "GPIO.1/RXT_13") (pintype "unspecified"))
    )
    (net (code "51") (name "SCL") (class "Default")
      (node (ref "CN3") (pin "1") (pinfunction "1_1") (pintype "unspecified"))
      (node (ref "R7") (pin "1") (pinfunction "1_1") (pintype "unspecified"))
      (node (ref "U11") (pin "6") (pinfunction "SCL_6") (pintype "unspecified"))
      (node (ref "U3") (pin "5") (pinfunction "PB15_5") (pintype "unspecified"))
      (node (ref "U4") (pin "4") (pinfunction "SCK_4") (pintype "unspecified"))
      (node (ref "U5") (pin "23") (pinfunction "SCL/SCLK_23") (pintype "unspecified"))
      (node (ref "U7") (pin "2") (pinfunction "SCL_2") (pintype "unspecified"))
    )
    (net (code "52") (name "SDA") (class "Default")
      (node (ref "CN3") (pin "2") (pinfunction "2_2") (pintype "unspecified"))
      (node (ref "R8") (pin "2") (pinfunction "2_2") (pintype "unspecified"))
      (node (ref "U11") (pin "5") (pinfunction "SDA_5") (pintype "unspecified"))
      (node (ref "U3") (pin "6") (pinfunction "PA15_6") (pintype "unspecified"))
      (node (ref "U4") (pin "3") (pinfunction "SDI_3") (pintype "unspecified"))
      (node (ref "U5") (pin "24") (pinfunction "SDA/SDI_24") (pintype "unspecified"))
      (node (ref "U7") (pin "1") (pinfunction "SDA_1") (pintype "unspecified"))
    )
    (net (code "53") (name "SWCLK") (class "Default")
      (node (ref "CN2") (pin "1") (pinfunction "1_1") (pintype "unspecified"))
      (node (ref "U3") (pin "4") (pinfunction "PA14_4") (pintype "unspecified"))
    )
    (net (code "54") (name "SWDIO") (class "Default")
      (node (ref "CN2") (pin "3") (pinfunction "3_3") (pintype "unspecified"))
      (node (ref "U3") (pin "3") (pinfunction "PA13_3") (pintype "unspecified"))
    )
    (net (code "55") (name "TXD") (class "Default")
      (node (ref "CN2") (pin "2") (pinfunction "2_2") (pintype "unspecified"))
      (node (ref "SW19") (pin "4") (pinfunction "B1_4") (pintype "input"))
      (node (ref "U10") (pin "21") (pinfunction "TXD_21") (pintype "unspecified"))
      (node (ref "U3") (pin "9") (pinfunction "PB7_9") (pintype "unspecified"))
    )
    (net (code "56") (name "TXT") (class "Default")
      (node (ref "LED2") (pin "1") (pinfunction "K_1") (pintype "unspecified"))
      (node (ref "U10") (pin "14") (pinfunction "GPIO.0/TXT_14") (pintype "unspecified"))
    )
    (net (code "57") (name "VBAT") (class "Default")
      (node (ref "C1") (pin "1") (pinfunction "1_1") (pintype "unspecified"))
      (node (ref "D1") (pin "1") (pinfunction "K_1") (pintype "unspecified"))
      (node (ref "M1") (pin "1") (pinfunction "+_1") (pintype "unspecified"))
      (node (ref "R13") (pin "2") (pinfunction "2_2") (pintype "unspecified"))
      (node (ref "SW20") (pin "2") (pinfunction "2_2") (pintype "unspecified"))
      (node (ref "U7") (pin "7") (pinfunction "SRN_7") (pintype "unspecified"))
    )
    (net (code "58") (name "VBAT_IN") (class "Default")
      (node (ref "C12") (pin "2") (pinfunction "2_2") (pintype "unspecified"))
      (node (ref "C3") (pin "2") (pinfunction "2_2") (pintype "input"))
      (node (ref "CN1") (pin "2") (pinfunction "2_2") (pintype "unspecified"))
      (node (ref "R13") (pin "1") (pinfunction "1_1") (pintype "unspecified"))
      (node (ref "U6") (pin "3") (pinfunction "VBAT_3") (pintype "unspecified"))
      (node (ref "U7") (pin "6") (pinfunction "BAT_6") (pintype "unspecified"))
      (node (ref "U7") (pin "8") (pinfunction "SRP_8") (pintype "unspecified"))
    )
    (net (code "59") (name "VDD") (class "Default")
      (node (ref "C14") (pin "1") (pinfunction "1_1") (pintype "input"))
      (node (ref "LED2") (pin "2") (pinfunction "A_2") (pintype "unspecified"))
      (node (ref "LED3") (pin "2") (pinfunction "A_2") (pintype "unspecified"))
      (node (ref "R17") (pin "1") (pinfunction "1_1") (pintype "unspecified"))
      (node (ref "U10") (pin "5") (pinfunction "VIO_5") (pintype "unspecified"))
      (node (ref "U10") (pin "6") (pinfunction "VDD_6") (pintype "unspecified"))
    )
    (net (code "60") (name "VIN") (class "Default")
      (node (ref "C2") (pin "2") (pinfunction "2_2") (pintype "input"))
      (node (ref "CN2") (pin "7") (pinfunction "7_7") (pintype "unspecified"))
      (node (ref "CN2") (pin "8") (pinfunction "8_8") (pintype "unspecified"))
      (node (ref "D2") (pin "5") (pinfunction "VBUS_5") (pintype "input"))
      (node (ref "LED1") (pin "2") (pinfunction "A_2") (pintype "unspecified"))
      (node (ref "U10") (pin "7") (pinfunction "VREGIN_7") (pintype "unspecified"))
      (node (ref "U10") (pin "8") (pinfunction "VBUS_8") (pintype "unspecified"))
      (node (ref "U6") (pin "4") (pinfunction "VDD_4") (pintype "unspecified"))
      (node (ref "USB1") (pin "A4B9") (pinfunction "VBUS_A4B9") (pintype "unspecified"))
      (node (ref "USB1") (pin "B4A9") (pinfunction "VBUS_B4A9") (pintype "unspecified"))
    )
    (net (code "61") (name "unconnected-(SW20-Pad1)") (class "Default")
      (node (ref "SW20") (pin "1") (pinfunction "1_1") (pintype "unspecified+no_connect"))
    )
    (net (code "62") (name "unconnected-(SW20-Pad4)") (class "Default")
      (node (ref "SW20") (pin "4") (pinfunction "4_4") (pintype "unspecified+no_connect"))
    )
    (net (code "63") (name "unconnected-(SW20-Pad5)") (class "Default")
      (node (ref "SW20") (pin "5") (pinfunction "5_5") (pintype "unspecified+no_connect"))
    )
    (net (code "64") (name "unconnected-(SW20-Pad6)") (class "Default")
      (node (ref "SW20") (pin "6") (pinfunction "6_6") (pintype "unspecified+no_connect"))
    )
    (net (code "65") (name "unconnected-(SW21-Pad4)") (class "Default")
      (node (ref "SW21") (pin "4") (pinfunction "4_4") (pintype "unspecified+no_connect"))
    )
    (net (code "66") (name "unconnected-(SW21-Pad5)") (class "Default")
      (node (ref "SW21") (pin "5") (pinfunction "5_5") (pintype "unspecified+no_connect"))
    )
    (net (code "67") (name "unconnected-(SW21-Pad6)") (class "Default")
      (node (ref "SW21") (pin "6") (pinfunction "6_6") (pintype "unspecified+no_connect"))
    )
    (net (code "68") (name "unconnected-(U1-Pad1)") (class "Default")
      (node (ref "U1") (pin "1") (pinfunction "1_1") (pintype "unspecified+no_connect"))
    )
    (net (code "69") (name "unconnected-(U1-Pad14)") (class "Default")
      (node (ref "U1") (pin "14") (pinfunction "14_14") (pintype "unspecified+no_connect"))
    )
    (net (code "70") (name "unconnected-(U2-1PPS-Pad6)") (class "Default")
      (node (ref "U2") (pin "6") (pinfunction "1PPS_6") (pintype "unspecified"))
    )
    (net (code "71") (name "unconnected-(U2-AADET_N-Pad8)") (class "Default")
      (node (ref "U2") (pin "8") (pinfunction "AADET_N_8") (pintype "unspecified"))
    )
    (net (code "72") (name "unconnected-(U2-EX_ANT-Pad11)") (class "Default")
      (node (ref "U2") (pin "11") (pinfunction "EX_ANT_11") (pintype "unspecified"))
    )
    (net (code "73") (name "unconnected-(U2-NC-Pad9)") (class "Default")
      (node (ref "U2") (pin "9") (pinfunction "NC_9") (pintype "unspecified"))
    )
    (net (code "74") (name "unconnected-(U2-RESET-Pad10)") (class "Default")
      (node (ref "U2") (pin "10") (pinfunction "RESET_10") (pintype "unspecified"))
    )
    (net (code "75") (name "unconnected-(U2-TIMER-Pad7)") (class "Default")
      (node (ref "U2") (pin "7") (pinfunction "TIMER_7") (pintype "unspecified"))
    )
    (net (code "76") (name "unconnected-(U3-PB0-Pad28)") (class "Default")
      (node (ref "U3") (pin "28") (pinfunction "PB0_28") (pintype "unspecified"))
    )
    (net (code "77") (name "unconnected-(U5-AUX_CL-Pad7)") (class "Default")
      (node (ref "U5") (pin "7") (pinfunction "AUX_CL_7") (pintype "unspecified+no_connect"))
    )
    (net (code "78") (name "unconnected-(U5-AUX_DA-Pad21)") (class "Default")
      (node (ref "U5") (pin "21") (pinfunction "AUX_DA_21") (pintype "unspecified+no_connect"))
    )
    (net (code "79") (name "unconnected-(U5-NC-Pad2)") (class "Default")
      (node (ref "U5") (pin "2") (pinfunction "NC_2") (pintype "unspecified+no_connect"))
    )
    (net (code "80") (name "unconnected-(U5-NC-Pad3)") (class "Default")
      (node (ref "U5") (pin "3") (pinfunction "NC_3") (pintype "unspecified+no_connect"))
    )
    (net (code "81") (name "unconnected-(U5-NC-Pad4)") (class "Default")
      (node (ref "U5") (pin "4") (pinfunction "NC_4") (pintype "unspecified+no_connect"))
    )
    (net (code "82") (name "unconnected-(U5-NC-Pad5)") (class "Default")
      (node (ref "U5") (pin "5") (pinfunction "NC_5") (pintype "unspecified+no_connect"))
    )
    (net (code "83") (name "unconnected-(U5-NC-Pad6)") (class "Default")
      (node (ref "U5") (pin "6") (pinfunction "NC_6") (pintype "unspecified+no_connect"))
    )
    (net (code "84") (name "unconnected-(U5-NC-Pad14)") (class "Default")
      (node (ref "U5") (pin "14") (pinfunction "NC_14") (pintype "unspecified+no_connect"))
    )
    (net (code "85") (name "unconnected-(U5-NC-Pad15)") (class "Default")
      (node (ref "U5") (pin "15") (pinfunction "NC_15") (pintype "unspecified+no_connect"))
    )
    (net (code "86") (name "unconnected-(U5-NC-Pad16)") (class "Default")
      (node (ref "U5") (pin "16") (pinfunction "NC_16") (pintype "unspecified+no_connect"))
    )
    (net (code "87") (name "unconnected-(U5-NC-Pad17)") (class "Default")
      (node (ref "U5") (pin "17") (pinfunction "NC_17") (pintype "unspecified+no_connect"))
    )
    (net (code "88") (name "unconnected-(U5-RESV-Pad19)") (class "Default")
      (node (ref "U5") (pin "19") (pinfunction "RESV_19") (pintype "unspecified+no_connect"))
    )
    (net (code "89") (name "unconnected-(U7-NC-Pad4)") (class "Default")
      (node (ref "U7") (pin "4") (pinfunction "NC_4") (pintype "unspecified+no_connect"))
    )
    (net (code "90") (name "unconnected-(U7-NC-Pad9)") (class "Default")
      (node (ref "U7") (pin "9") (pinfunction "NC_9") (pintype "unspecified+no_connect"))
    )
    (net (code "91") (name "unconnected-(U7-NC-Pad11)") (class "Default")
      (node (ref "U7") (pin "11") (pinfunction "NC_11") (pintype "unspecified+no_connect"))
    )
    (net (code "92") (name "unconnected-(U8-NC-Pad4)") (class "Default")
      (node (ref "U8") (pin "4") (pinfunction "NC_4") (pintype "unspecified+no_connect"))
    )
    (net (code "93") (name "unconnected-(U10-CTS-Pad18)") (class "Default")
      (node (ref "U10") (pin "18") (pinfunction "CTS_18") (pintype "unspecified"))
    )
    (net (code "94") (name "unconnected-(U10-DCD-Pad24)") (class "Default")
      (node (ref "U10") (pin "24") (pinfunction "DCD_24") (pintype "unspecified"))
    )
    (net (code "95") (name "unconnected-(U10-DSR-Pad22)") (class "Default")
      (node (ref "U10") (pin "22") (pinfunction "DSR_22") (pintype "unspecified"))
    )
    (net (code "96") (name "unconnected-(U10-GPIO.2{slash}RS485-Pad12)") (class "Default")
      (node (ref "U10") (pin "12") (pinfunction "GPIO.2/RS485_12") (pintype "unspecified"))
    )
    (net (code "97") (name "unconnected-(U10-GPIO.3{slash}WAKEUP-Pad11)") (class "Default")
      (node (ref "U10") (pin "11") (pinfunction "GPIO.3/WAKEUP_11") (pintype "unspecified"))
    )
    (net (code "98") (name "unconnected-(U10-NC-Pad10)") (class "Default")
      (node (ref "U10") (pin "10") (pinfunction "NC_10") (pintype "unspecified+no_connect"))
    )
    (net (code "99") (name "unconnected-(U10-NC-Pad16)") (class "Default")
      (node (ref "U10") (pin "16") (pinfunction "NC_16") (pintype "unspecified"))
    )
    (net (code "100") (name "unconnected-(U10-RI{slash}CLK-Pad1)") (class "Default")
      (node (ref "U10") (pin "1") (pinfunction "RI/CLK_1") (pintype "unspecified"))
    )
    (net (code "101") (name "unconnected-(U10-RTS-Pad19)") (class "Default")
      (node (ref "U10") (pin "19") (pinfunction "RTS_19") (pintype "unspecified"))
    )
    (net (code "102") (name "unconnected-(U10-SUSPEND-Pad17)") (class "Default")
      (node (ref "U10") (pin "17") (pinfunction "SUSPEND_17") (pintype "unspecified"))
    )
    (net (code "103") (name "unconnected-(U10-SUSPENDb-Pad15)") (class "Default")
      (node (ref "U10") (pin "15") (pinfunction "SUSPENDb_15") (pintype "unspecified"))
    )
    (net (code "104") (name "unconnected-(U11-WC#-Pad7)") (class "Default")
      (node (ref "U11") (pin "7") (pinfunction "WC#_7") (pintype "unspecified+no_connect"))
    )
    (net (code "105") (name "unconnected-(USB1-SBU1-PadA8)") (class "Default")
      (node (ref "USB1") (pin "A8") (pinfunction "SBU1_A8") (pintype "unspecified+no_connect"))
    )
    (net (code "106") (name "unconnected-(USB1-SBU2-PadB8)") (class "Default")
      (node (ref "USB1") (pin "B8") (pinfunction "SBU2_B8") (pintype "unspecified+no_connect"))
    )
  )
)
